# kinx.net
KiCad netlist of a schematic drawn in EAGLE
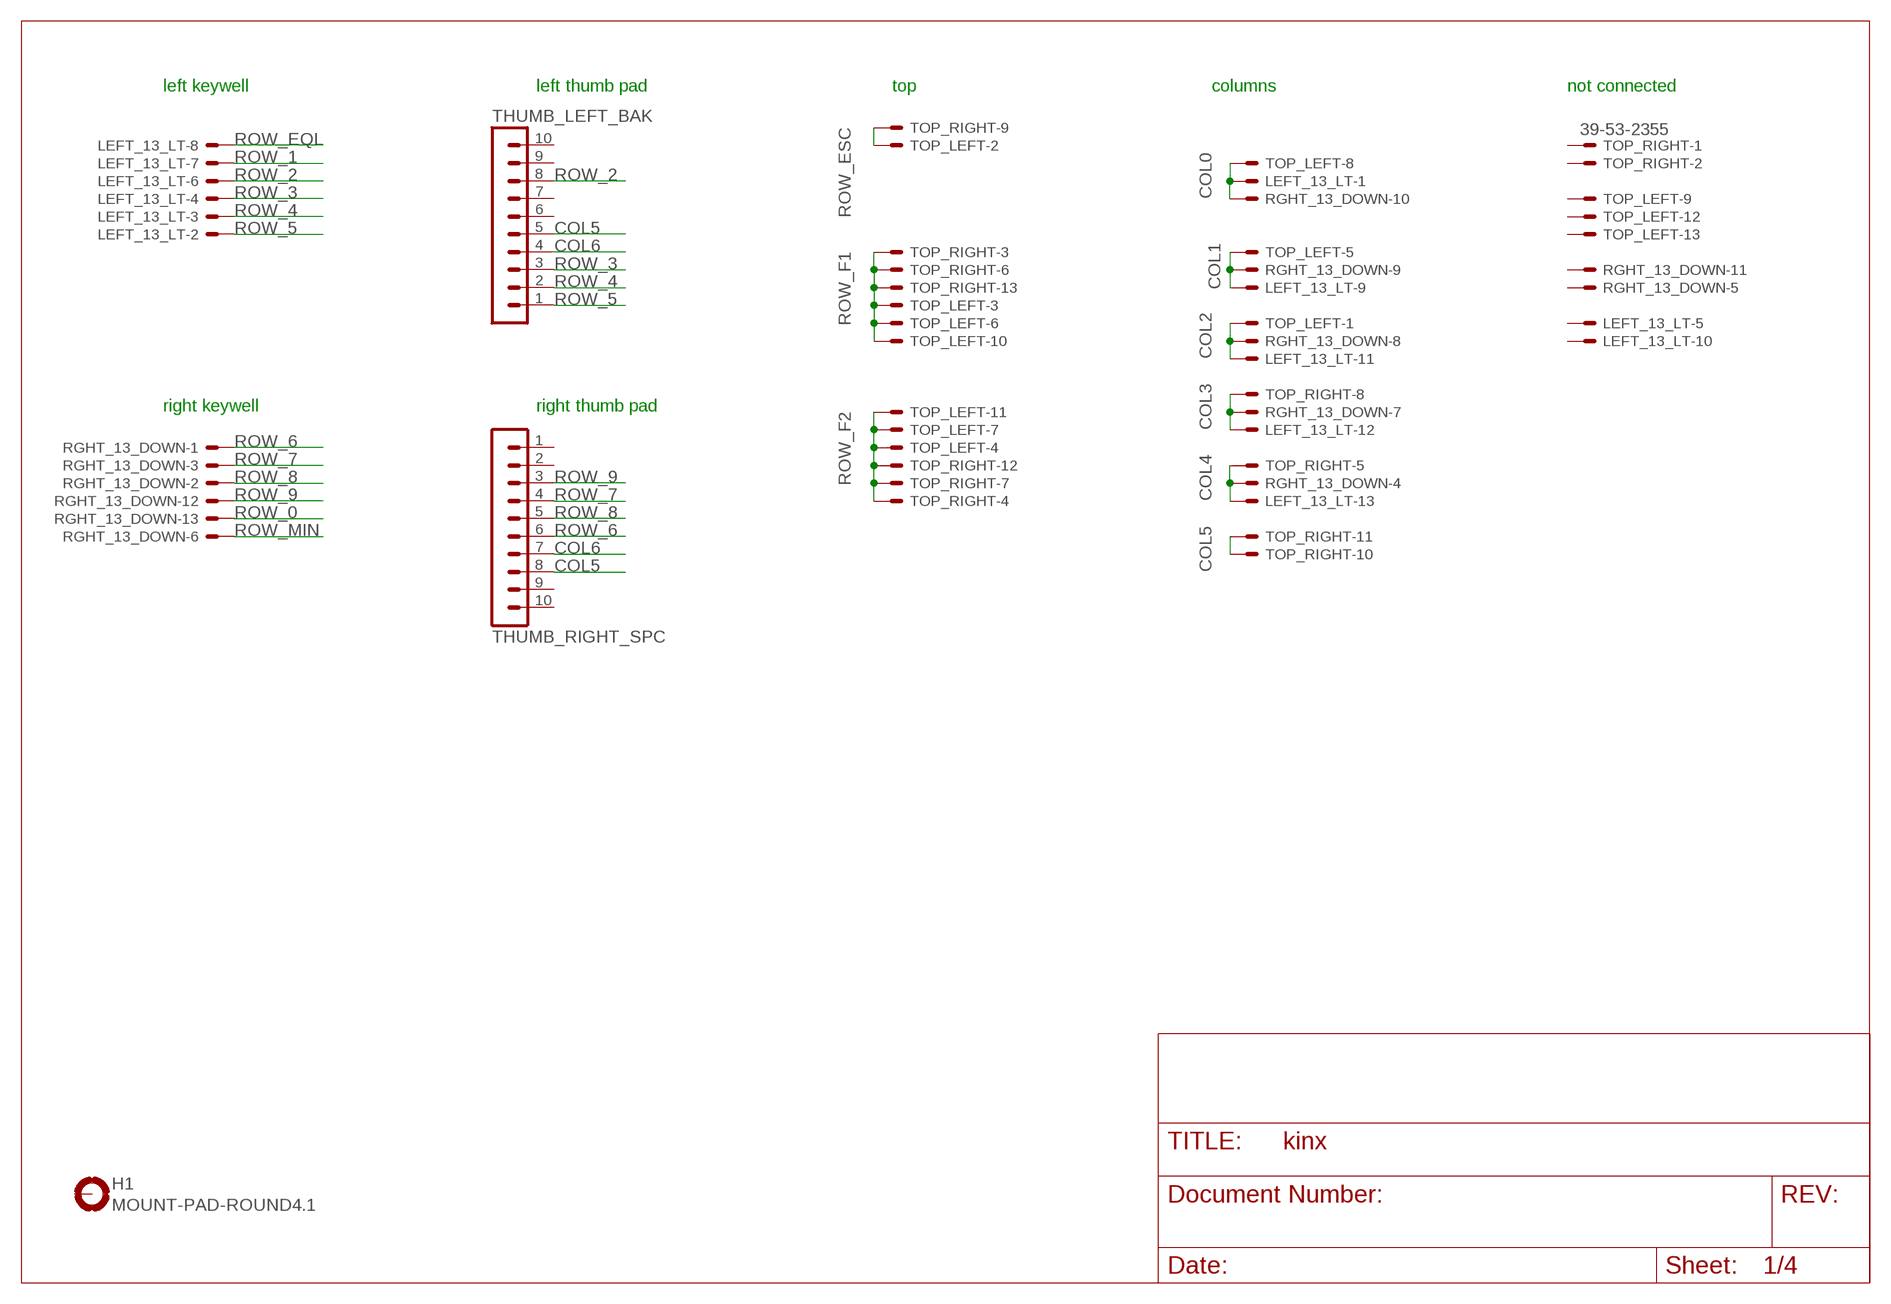
[diagram p0: schematic, sheet 1]
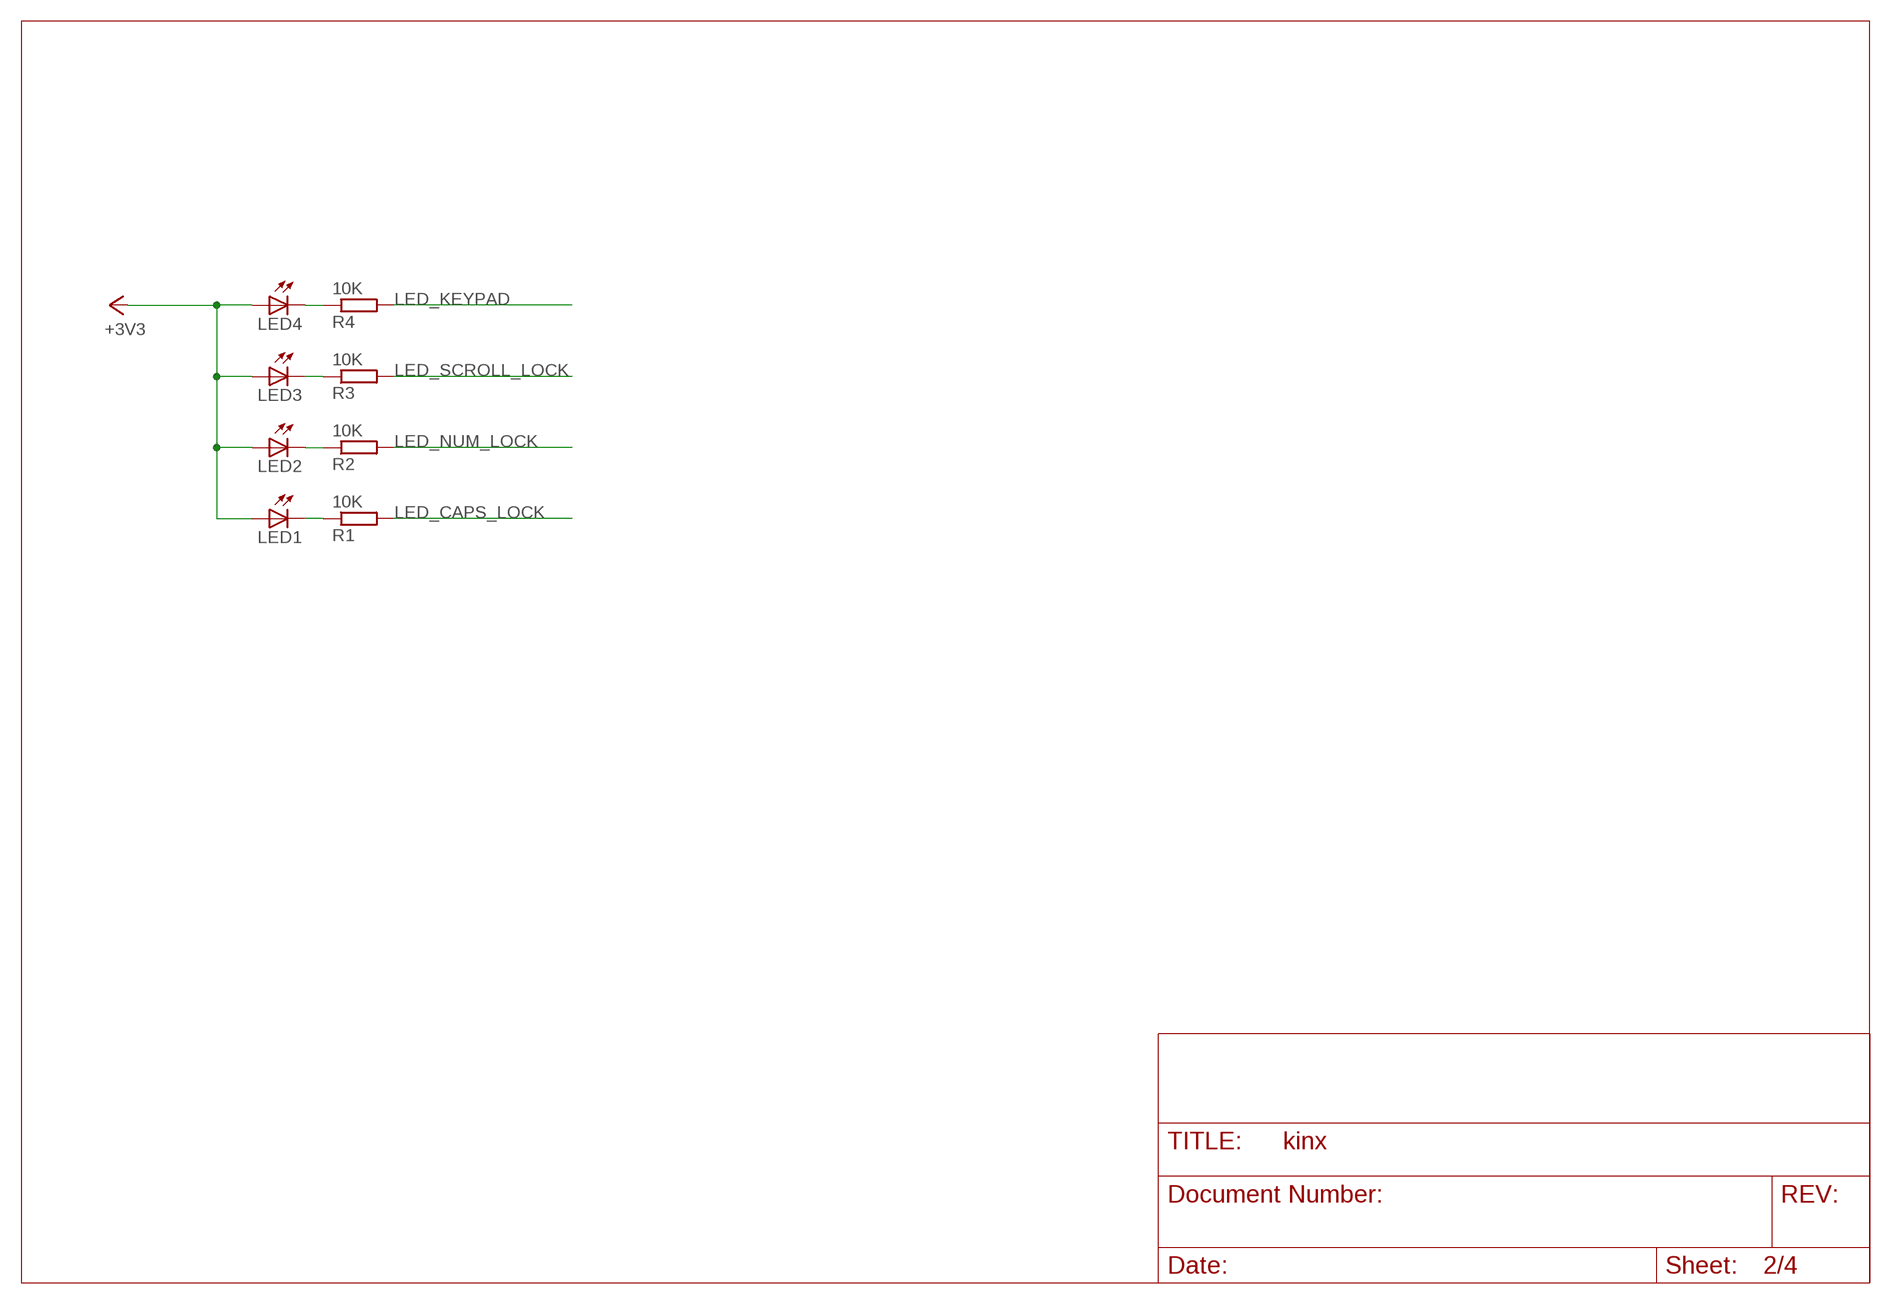
[diagram p1: schematic, sheet 2]
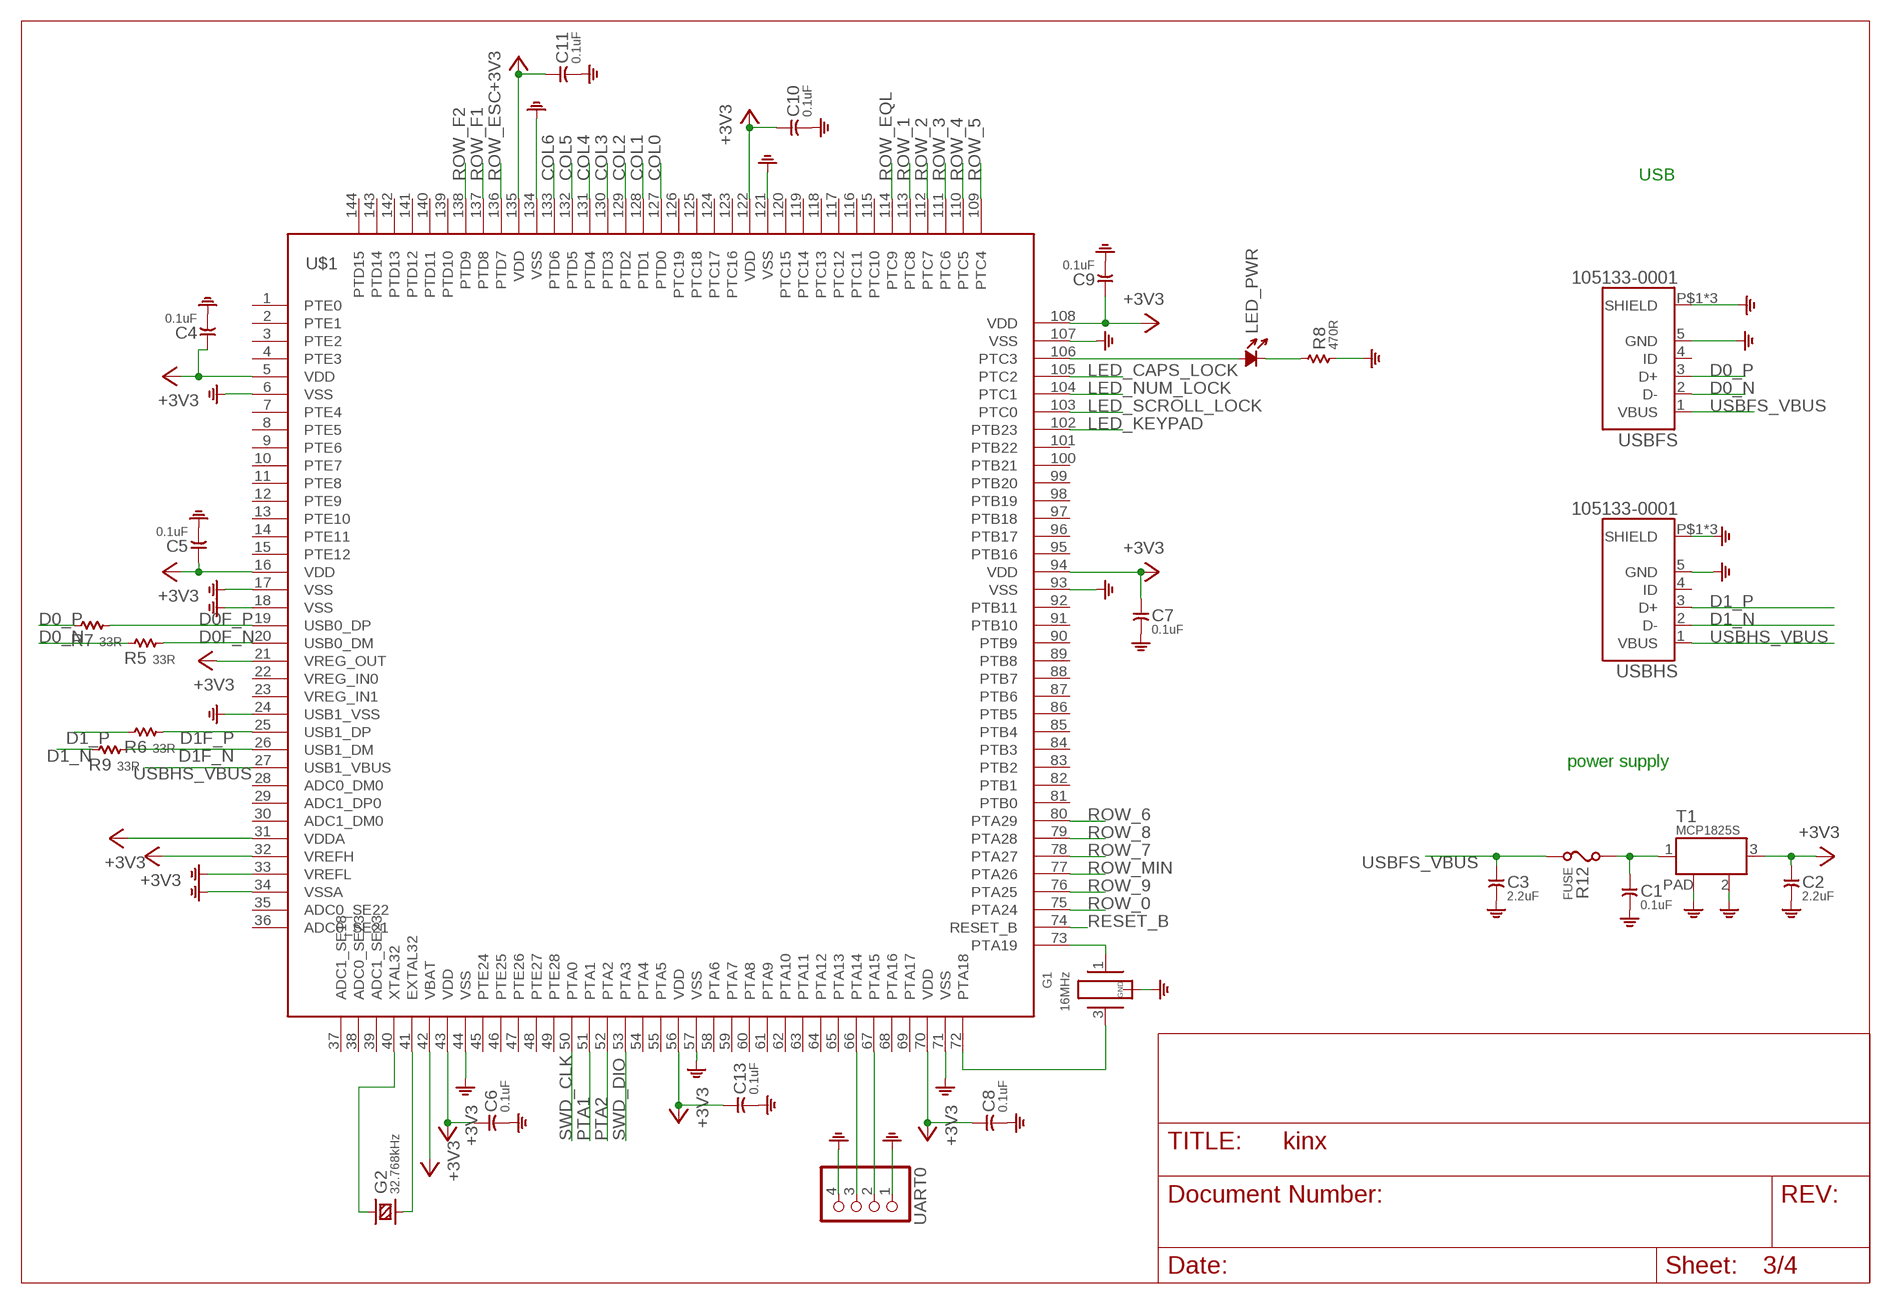
[diagram p2: schematic, sheet 3]
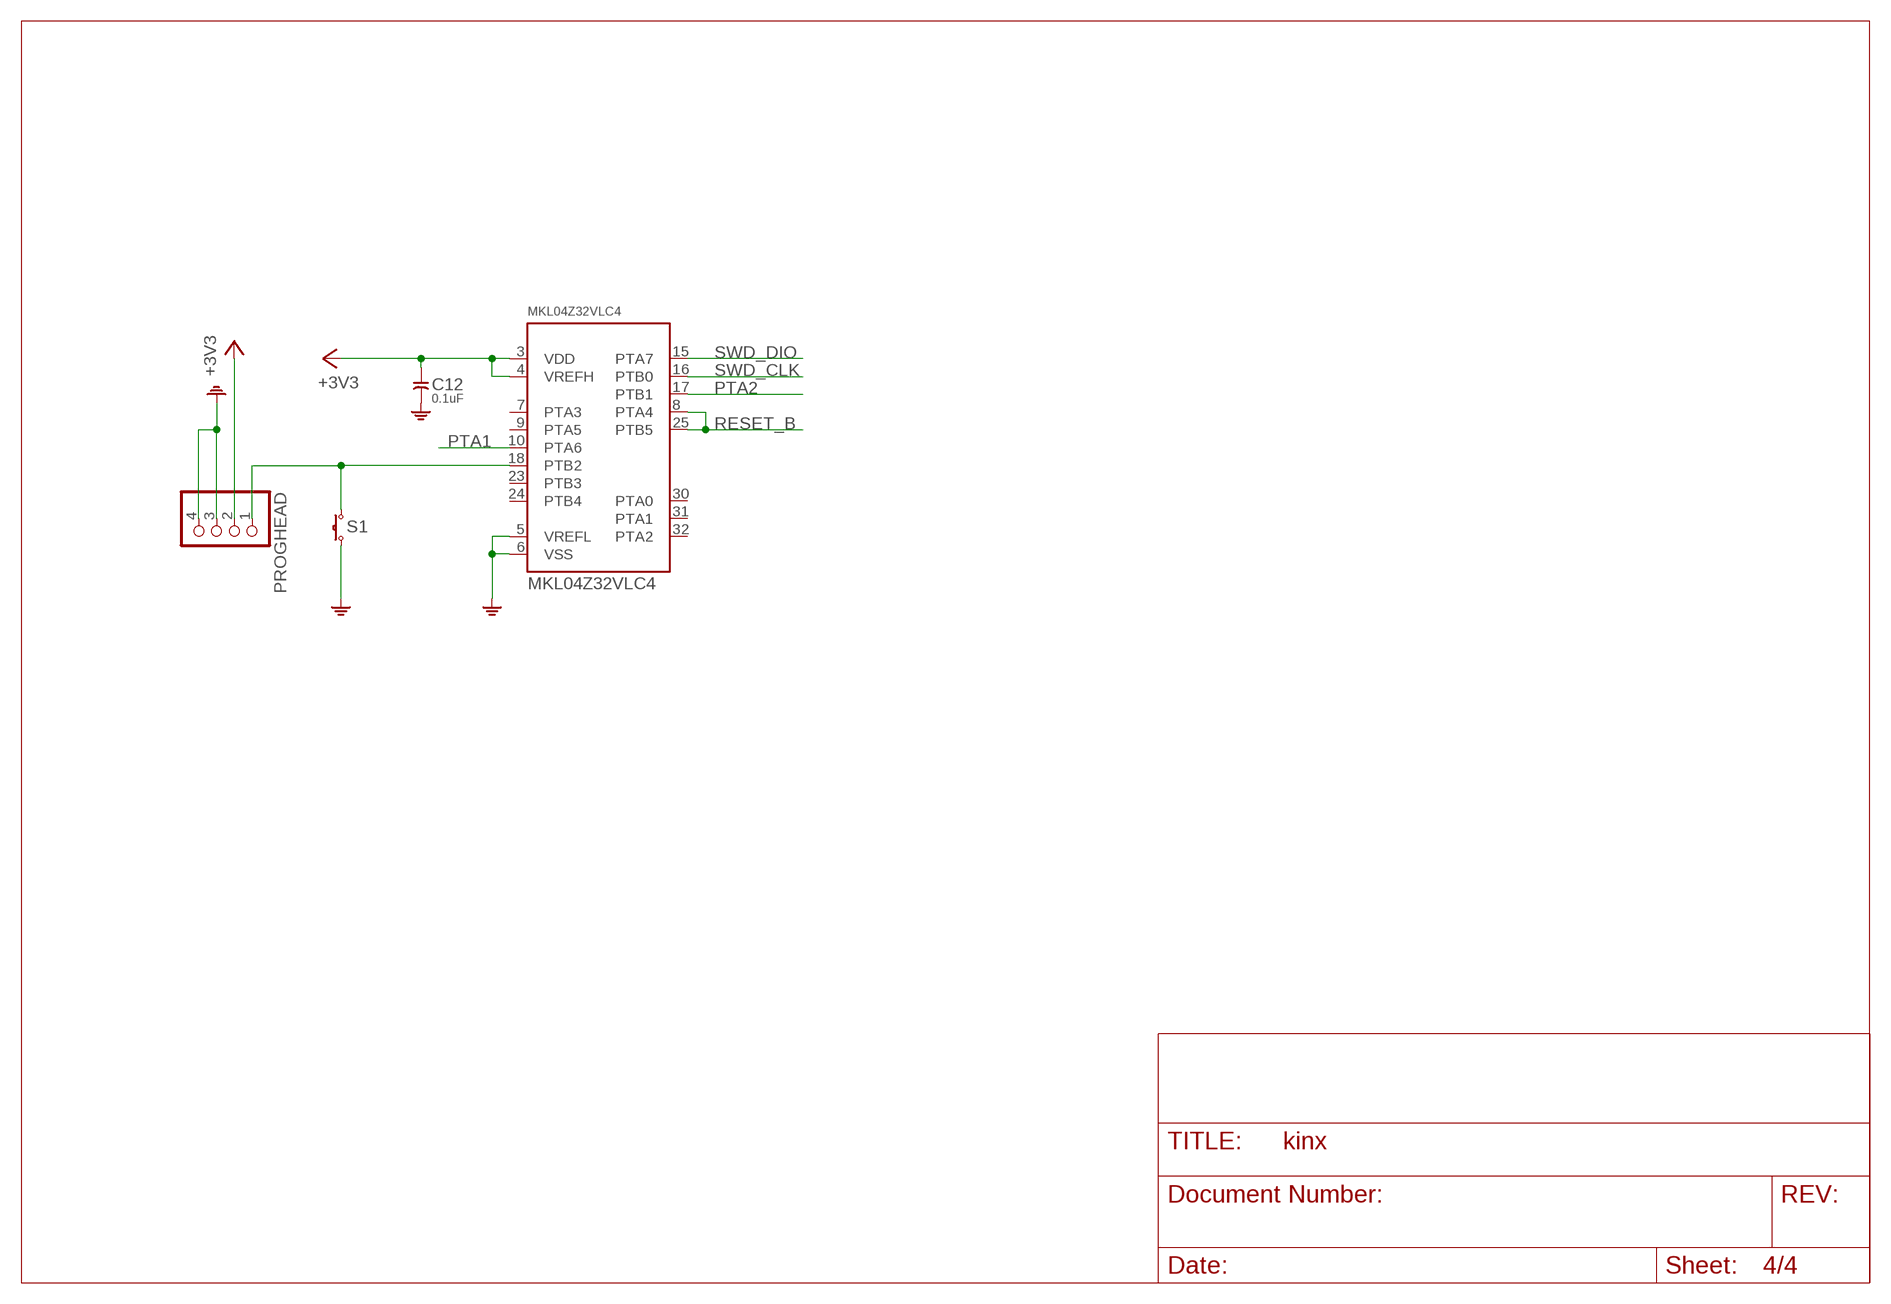
[diagram p3: schematic, sheet 4]

(export (version "E")
  (design (tool "Eeschema 10.0.6"))
  (components
    (comp (ref "LED1")
      (value "LEDSML1206")
      (footprint "eagle-import:SML1206")
      (libsource (lib "eagle-import") (part "LEDSML1206"))
    )
    (comp (ref "LED2")
      (value "LEDSML1206")
      (footprint "eagle-import:SML1206")
      (libsource (lib "eagle-import") (part "LEDSML1206"))
    )
    (comp (ref "LED3")
      (value "LEDSML1206")
      (footprint "eagle-import:SML1206")
      (libsource (lib "eagle-import") (part "LEDSML1206"))
    )
    (comp (ref "LED4")
      (value "LEDSML1206")
      (footprint "eagle-import:SML1206")
      (libsource (lib "eagle-import") (part "LEDSML1206"))
    )
    (comp (ref "R1")
      (value "10K")
      (footprint "eagle-import:R1206")
      (libsource (lib "eagle-import") (part "R-EU_R1206"))
    )
    (comp (ref "R2")
      (value "10K")
      (footprint "eagle-import:R1206")
      (libsource (lib "eagle-import") (part "R-EU_R1206"))
    )
    (comp (ref "R3")
      (value "10K")
      (footprint "eagle-import:R1206")
      (libsource (lib "eagle-import") (part "R-EU_R1206"))
    )
    (comp (ref "R4")
      (value "10K")
      (footprint "eagle-import:R1206")
      (libsource (lib "eagle-import") (part "R-EU_R1206"))
    )
    (comp (ref "C12")
      (value "0.1uF")
      (footprint "eagle-import:C0603")
      (fields (field (name "MF") "Murata Electronics") (field (name "MPN") "GRM188R71C104KA01D"))
      (libsource (lib "eagle-import") (part "CAPACITOR-0.1UF"))
    )
    (comp (ref "MKL04Z32VLC4")
      (value "MKL04Z32VLC4")
      (footprint "eagle-import:LQFP32-08")
      (fields (field (name "MF") "PJRC") (field (name "MPN") "IC_MKL04Z32_TQFP32"))
      (libsource (lib "eagle-import") (part "MKL04Z32VLC4"))
    )
    (comp (ref "PROGHEAD")
      (value "PINHD-1X4/90")
      (footprint "eagle-import:1X04_90")
      (libsource (lib "eagle-import") (part "PINHD-1X4/90"))
    )
    (comp (ref "S1")
      (value "TACT_SWITCH")
      (footprint "eagle-import:ALPS_SKHH")
      (fields (field (name "MF") "ALPS") (field (name "MPN") "SKHHPKA010"))
      (libsource (lib "eagle-import") (part "TACT_SWITCH"))
    )
    (comp (ref "C1")
      (value "0.1uF")
      (footprint "eagle-import:C0603")
      (fields (field (name "MF") "Murata Electronics") (field (name "MPN") "GRM188R71C104KA01D"))
      (libsource (lib "eagle-import") (part "CAPACITOR-0.1UF"))
    )
    (comp (ref "C2")
      (value "2.2uF")
      (footprint "eagle-import:C0805")
      (fields (field (name "MF") "Taiyo Yuden") (field (name "MPN") "TMK212B7225KG-TR"))
      (libsource (lib "eagle-import") (part "CAPACITOR-2.2UF"))
    )
    (comp (ref "C3")
      (value "2.2uF")
      (footprint "eagle-import:C0805")
      (fields (field (name "MF") "Taiyo Yuden") (field (name "MPN") "TMK212B7225KG-TR"))
      (libsource (lib "eagle-import") (part "CAPACITOR-2.2UF"))
    )
    (comp (ref "C4")
      (value "0.1uF")
      (footprint "eagle-import:C0603")
      (fields (field (name "MF") "Murata Electronics") (field (name "MPN") "GRM188R71C104KA01D"))
      (libsource (lib "eagle-import") (part "CAPACITOR-0.1UF"))
    )
    (comp (ref "C5")
      (value "0.1uF")
      (footprint "eagle-import:C0603")
      (fields (field (name "MF") "Murata Electronics") (field (name "MPN") "GRM188R71C104KA01D"))
      (libsource (lib "eagle-import") (part "CAPACITOR-0.1UF"))
    )
    (comp (ref "C6")
      (value "0.1uF")
      (footprint "eagle-import:C0603")
      (fields (field (name "MF") "Murata Electronics") (field (name "MPN") "GRM188R71C104KA01D"))
      (libsource (lib "eagle-import") (part "CAPACITOR-0.1UF"))
    )
    (comp (ref "C7")
      (value "0.1uF")
      (footprint "eagle-import:C0603")
      (fields (field (name "MF") "Murata Electronics") (field (name "MPN") "GRM188R71C104KA01D"))
      (libsource (lib "eagle-import") (part "CAPACITOR-0.1UF"))
    )
    (comp (ref "C8")
      (value "0.1uF")
      (footprint "eagle-import:C0603")
      (fields (field (name "MF") "Murata Electronics") (field (name "MPN") "GRM188R71C104KA01D"))
      (libsource (lib "eagle-import") (part "CAPACITOR-0.1UF"))
    )
    (comp (ref "C9")
      (value "0.1uF")
      (footprint "eagle-import:C0603")
      (fields (field (name "MF") "Murata Electronics") (field (name "MPN") "GRM188R71C104KA01D"))
      (libsource (lib "eagle-import") (part "CAPACITOR-0.1UF"))
    )
    (comp (ref "C10")
      (value "0.1uF")
      (footprint "eagle-import:C0603")
      (fields (field (name "MF") "Murata Electronics") (field (name "MPN") "GRM188R71C104KA01D"))
      (libsource (lib "eagle-import") (part "CAPACITOR-0.1UF"))
    )
    (comp (ref "C11")
      (value "0.1uF")
      (footprint "eagle-import:C0603")
      (fields (field (name "MF") "Murata Electronics") (field (name "MPN") "GRM188R71C104KA01D"))
      (libsource (lib "eagle-import") (part "CAPACITOR-0.1UF"))
    )
    (comp (ref "C13")
      (value "0.1uF")
      (footprint "eagle-import:C0603")
      (fields (field (name "MF") "Murata Electronics") (field (name "MPN") "GRM188R71C104KA01D"))
      (libsource (lib "eagle-import") (part "CAPACITOR-0.1UF"))
    )
    (comp (ref "G1")
      (value "16MHz")
      (footprint "eagle-import:FHXXX")
      (fields
        (field (name "MANUFACTURER") "Diodes Incorporated")
        (field (name "MPN") "FH1600015")
        (field (name "DIGIKEY") "SER4068CT-ND")
      )
      (libsource (lib "eagle-import") (part "FH1600015"))
    )
    (comp (ref "G2")
      (value "32.768kHz")
      (footprint "eagle-import:TC26H")
      (fields (field (name "MF") "Citizen FineDevice") (field (name "MPN") " CFS206-32.768KDZF-UB"))
      (libsource (lib "eagle-import") (part "CRYSTAL-TC26H"))
    )
    (comp (ref "LED_PWR")
      (value "LED")
      (footprint "eagle-import:LED-0805")
      (fields (field (name "MF") "ROHM Semiconductor") (field (name "MPN") "SML-211DTT86"))
      (libsource (lib "eagle-import") (part "t32_ref_LED"))
    )
    (comp (ref "R5")
      (value "33R")
      (footprint "eagle-import:R0603")
      (fields (field (name "MF") "Panasonic") (field (name "MPN") "ERJ-PA3F33R0V"))
      (libsource (lib "eagle-import") (part "RESISTOR-33R"))
    )
    (comp (ref "R6")
      (value "33R")
      (footprint "eagle-import:R0603")
      (fields (field (name "MF") "Panasonic") (field (name "MPN") "ERJ-PA3F33R0V"))
      (libsource (lib "eagle-import") (part "RESISTOR-33R"))
    )
    (comp (ref "R7")
      (value "33R")
      (footprint "eagle-import:R0603")
      (fields (field (name "MF") "Panasonic") (field (name "MPN") "ERJ-PA3F33R0V"))
      (libsource (lib "eagle-import") (part "RESISTOR-33R"))
    )
    (comp (ref "R8")
      (value "470R")
      (footprint "eagle-import:R0603")
      (fields (field (name "MF") "Vishay") (field (name "MPN") "CRCW0603470RFKEA"))
      (libsource (lib "eagle-import") (part "RESISTOR-470R"))
    )
    (comp (ref "R9")
      (value "33R")
      (footprint "eagle-import:R0603")
      (fields (field (name "MF") "Panasonic") (field (name "MPN") "ERJ-PA3F33R0V"))
      (libsource (lib "eagle-import") (part "RESISTOR-33R"))
    )
    (comp (ref "R12")
      (value "FUSE")
      (footprint "eagle-import:F0805")
      (fields (field (name "MF") "Bel Fuse") (field (name "MPN") "0ZCK0050FF2E"))
      (libsource (lib "eagle-import") (part "FUSE"))
    )
    (comp (ref "T1")
      (value "MCP1825S")
      (footprint "eagle-import:SOT-223")
      (fields (field (name "MF") "Microchip Technology") (field (name "MPN") "MCP1825S-3302E/DB"))
      (libsource (lib "eagle-import") (part "LDO"))
    )
    (comp (ref "U$1")
      (value "MK66FX1M0VLQ18")
      (footprint "eagle-import:TQFP144")
      (libsource (lib "eagle-import") (part "MK66FX1M0VLQ18"))
    )
    (comp (ref "UART0")
      (value "PINHD-1X4/90")
      (footprint "eagle-import:1X04_90")
      (libsource (lib "eagle-import") (part "PINHD-1X4/90"))
    )
    (comp (ref "USBFS")
      (value "105133-0001")
      (footprint "eagle-import:MOLEX_105133-0001")
      (fields (field (name "MF") "Molex") (field (name "MP") "105133-0011"))
      (libsource (lib "eagle-import") (part "105133-0001"))
    )
    (comp (ref "USBHS")
      (value "105133-0001")
      (footprint "eagle-import:MOLEX_105133-0001")
      (fields (field (name "MF") "Molex") (field (name "MP") "105133-0011"))
      (libsource (lib "eagle-import") (part "105133-0001"))
    )
    (comp (ref "H1")
      (value "MOUNT-PAD-ROUND4.1")
      (footprint "eagle-import:4,1-PAD")
      (libsource (lib "eagle-import") (part "MOUNT-PAD-ROUND4.1"))
    )
    (comp (ref "LEFT_13_LT")
      (value "39-53-2355")
      (footprint "eagle-import:39-53-2135")
      (fields (field (name "OC_MOUSER") "538-39-53-2135") (field (name "DIGIKEY") "WM14526-ND"))
      (libsource (lib "eagle-import") (part "39-53-2355"))
    )
    (comp (ref "RGHT_13_DOWN")
      (value "39-53-2355")
      (footprint "eagle-import:39-53-2135")
      (fields (field (name "DIGIKEY") "WM14526-ND") (field (name "OC_MOUSER") "538-39-53-2135"))
      (libsource (lib "eagle-import") (part "39-53-2355"))
    )
    (comp (ref "THUMB_LEFT_BAK")
      (value "MA10-1")
      (footprint "eagle-import:MA10-1")
      (libsource (lib "eagle-import") (part "MA10-1"))
    )
    (comp (ref "THUMB_RIGHT_SPC")
      (value "MA10-1")
      (footprint "eagle-import:MA10-1")
      (libsource (lib "eagle-import") (part "MA10-1"))
    )
    (comp (ref "TOP_LEFT")
      (value "39-53-2355")
      (footprint "eagle-import:39-53-2135")
      (fields (field (name "DIGIKEY") "WM14526-ND") (field (name "OC_MOUSER") "538-39-53-2135"))
      (libsource (lib "eagle-import") (part "39-53-2355"))
    )
    (comp (ref "TOP_RIGHT")
      (value "39-53-2355")
      (footprint "eagle-import:39-53-2135")
      (fields (field (name "DIGIKEY") "WM14526-ND") (field (name "OC_MOUSER") "538-39-53-2135"))
      (libsource (lib "eagle-import") (part "39-53-2355"))
    )
  )
  (nets
    (net (code "1") (name "+3V3") (class "Default")
      (node (ref "C10") (pin "1") (pinfunction "1_1") (pintype "passive"))
      (node (ref "C11") (pin "1") (pinfunction "1_1") (pintype "passive"))
      (node (ref "C12") (pin "1") (pinfunction "1_1") (pintype "passive"))
      (node (ref "C13") (pin "1") (pinfunction "1_1") (pintype "passive"))
      (node (ref "C2") (pin "1") (pinfunction "1_1") (pintype "passive"))
      (node (ref "C4") (pin "1") (pinfunction "1_1") (pintype "passive"))
      (node (ref "C5") (pin "1") (pinfunction "1_1") (pintype "passive"))
      (node (ref "C6") (pin "1") (pinfunction "1_1") (pintype "passive"))
      (node (ref "C7") (pin "1") (pinfunction "1_1") (pintype "passive"))
      (node (ref "C8") (pin "1") (pinfunction "1_1") (pintype "passive"))
      (node (ref "C9") (pin "1") (pinfunction "1_1") (pintype "passive"))
      (node (ref "LED1") (pin "A") (pinfunction "A_A") (pintype "passive"))
      (node (ref "LED2") (pin "A") (pinfunction "A_A") (pintype "passive"))
      (node (ref "LED3") (pin "A") (pinfunction "A_A") (pintype "passive"))
      (node (ref "LED4") (pin "A") (pinfunction "A_A") (pintype "passive"))
      (node (ref "MKL04Z32VLC4") (pin "3") (pinfunction "VDD_3") (pintype "bidirectional"))
      (node (ref "MKL04Z32VLC4") (pin "4") (pinfunction "VREFH_4") (pintype "bidirectional"))
      (node (ref "PROGHEAD") (pin "2") (pinfunction "2_2") (pintype "passive"))
      (node (ref "T1") (pin "3") (pinfunction "OUT_3") (pintype "bidirectional"))
      (node (ref "U$1") (pin "108") (pinfunction "VDD_108") (pintype "power_in"))
      (node (ref "U$1") (pin "122") (pinfunction "VDD_122") (pintype "power_in"))
      (node (ref "U$1") (pin "135") (pinfunction "VDD_135") (pintype "power_in"))
      (node (ref "U$1") (pin "16") (pinfunction "VDD_16") (pintype "power_in"))
      (node (ref "U$1") (pin "21") (pinfunction "VREG_OUT_21") (pintype "power_in"))
      (node (ref "U$1") (pin "31") (pinfunction "VDDA_31") (pintype "power_in"))
      (node (ref "U$1") (pin "32") (pinfunction "VREFH_32") (pintype "bidirectional"))
      (node (ref "U$1") (pin "42") (pinfunction "VBAT_42") (pintype "power_in"))
      (node (ref "U$1") (pin "43") (pinfunction "VDD_43") (pintype "power_in"))
      (node (ref "U$1") (pin "5") (pinfunction "VDD_5") (pintype "power_in"))
      (node (ref "U$1") (pin "56") (pinfunction "VDD_56") (pintype "power_in"))
      (node (ref "U$1") (pin "70") (pinfunction "VDD_70") (pintype "power_in"))
      (node (ref "U$1") (pin "94") (pinfunction "VDD_94") (pintype "power_in"))
    )
    (net (code "2") (name "COL0") (class "Default")
      (node (ref "LEFT_13_LT") (pin "P$1") (pinfunction "S_P$1") (pintype "passive"))
      (node (ref "RGHT_13_DOWN") (pin "P$10") (pinfunction "S_P$10") (pintype "passive"))
      (node (ref "TOP_LEFT") (pin "P$8") (pinfunction "S_P$8") (pintype "passive"))
      (node (ref "U$1") (pin "127") (pinfunction "PTD0_127") (pintype "bidirectional"))
    )
    (net (code "3") (name "COL1") (class "Default")
      (node (ref "LEFT_13_LT") (pin "P$9") (pinfunction "S_P$9") (pintype "passive"))
      (node (ref "RGHT_13_DOWN") (pin "P$9") (pinfunction "S_P$9") (pintype "passive"))
      (node (ref "TOP_LEFT") (pin "P$5") (pinfunction "S_P$5") (pintype "passive"))
      (node (ref "U$1") (pin "128") (pinfunction "PTD1_128") (pintype "bidirectional"))
    )
    (net (code "4") (name "COL2") (class "Default")
      (node (ref "LEFT_13_LT") (pin "P$11") (pinfunction "S_P$11") (pintype "passive"))
      (node (ref "RGHT_13_DOWN") (pin "P$8") (pinfunction "S_P$8") (pintype "passive"))
      (node (ref "TOP_LEFT") (pin "P$1") (pinfunction "S_P$1") (pintype "passive"))
      (node (ref "U$1") (pin "129") (pinfunction "PTD2_129") (pintype "bidirectional"))
    )
    (net (code "5") (name "COL3") (class "Default")
      (node (ref "LEFT_13_LT") (pin "P$12") (pinfunction "S_P$12") (pintype "passive"))
      (node (ref "RGHT_13_DOWN") (pin "P$7") (pinfunction "S_P$7") (pintype "passive"))
      (node (ref "TOP_RIGHT") (pin "P$8") (pinfunction "S_P$8") (pintype "passive"))
      (node (ref "U$1") (pin "130") (pinfunction "PTD3_130") (pintype "bidirectional"))
    )
    (net (code "6") (name "COL4") (class "Default")
      (node (ref "LEFT_13_LT") (pin "P$13") (pinfunction "S_P$13") (pintype "passive"))
      (node (ref "RGHT_13_DOWN") (pin "P$4") (pinfunction "S_P$4") (pintype "passive"))
      (node (ref "TOP_RIGHT") (pin "P$5") (pinfunction "S_P$5") (pintype "passive"))
      (node (ref "U$1") (pin "131") (pinfunction "PTD4_131") (pintype "bidirectional"))
    )
    (net (code "7") (name "COL5") (class "Default")
      (node (ref "THUMB_LEFT_BAK") (pin "5") (pinfunction "5_5") (pintype "passive"))
      (node (ref "THUMB_RIGHT_SPC") (pin "8") (pinfunction "8_8") (pintype "passive"))
      (node (ref "TOP_RIGHT") (pin "P$10") (pinfunction "S_P$10") (pintype "passive"))
      (node (ref "TOP_RIGHT") (pin "P$11") (pinfunction "S_P$11") (pintype "passive"))
      (node (ref "U$1") (pin "132") (pinfunction "PTD5_132") (pintype "bidirectional"))
    )
    (net (code "8") (name "COL6") (class "Default")
      (node (ref "THUMB_LEFT_BAK") (pin "4") (pinfunction "4_4") (pintype "passive"))
      (node (ref "THUMB_RIGHT_SPC") (pin "7") (pinfunction "7_7") (pintype "passive"))
      (node (ref "U$1") (pin "133") (pinfunction "PTD6_133") (pintype "bidirectional"))
    )
    (net (code "9") (name "D0F_N") (class "Default")
      (node (ref "R5") (pin "2") (pinfunction "2_2") (pintype "passive"))
      (node (ref "U$1") (pin "20") (pinfunction "USB0_DM_20") (pintype "bidirectional"))
    )
    (net (code "10") (name "D0F_P") (class "Default")
      (node (ref "R7") (pin "2") (pinfunction "2_2") (pintype "passive"))
      (node (ref "U$1") (pin "19") (pinfunction "USB0_DP_19") (pintype "bidirectional"))
    )
    (net (code "11") (name "D0_N") (class "Default")
      (node (ref "R5") (pin "1") (pinfunction "1_1") (pintype "passive"))
      (node (ref "USBFS") (pin "2") (pinfunction "D-_2") (pintype "bidirectional"))
    )
    (net (code "12") (name "D0_P") (class "Default")
      (node (ref "R7") (pin "1") (pinfunction "1_1") (pintype "passive"))
      (node (ref "USBFS") (pin "3") (pinfunction "D+_3") (pintype "bidirectional"))
    )
    (net (code "13") (name "D1F_N") (class "Default")
      (node (ref "R9") (pin "2") (pinfunction "2_2") (pintype "passive"))
      (node (ref "U$1") (pin "26") (pinfunction "USB1_DM_26") (pintype "bidirectional"))
    )
    (net (code "14") (name "D1F_P") (class "Default")
      (node (ref "R6") (pin "2") (pinfunction "2_2") (pintype "passive"))
      (node (ref "U$1") (pin "25") (pinfunction "USB1_DP_25") (pintype "bidirectional"))
    )
    (net (code "15") (name "D1_N") (class "Default")
      (node (ref "R9") (pin "1") (pinfunction "1_1") (pintype "passive"))
      (node (ref "USBHS") (pin "2") (pinfunction "D-_2") (pintype "bidirectional"))
    )
    (net (code "16") (name "D1_P") (class "Default")
      (node (ref "R6") (pin "1") (pinfunction "1_1") (pintype "passive"))
      (node (ref "USBHS") (pin "3") (pinfunction "D+_3") (pintype "bidirectional"))
    )
    (net (code "17") (name "GND") (class "Default")
      (node (ref "C1") (pin "2") (pinfunction "2_2") (pintype "passive"))
      (node (ref "C10") (pin "2") (pinfunction "2_2") (pintype "passive"))
      (node (ref "C11") (pin "2") (pinfunction "2_2") (pintype "passive"))
      (node (ref "C12") (pin "2") (pinfunction "2_2") (pintype "passive"))
      (node (ref "C13") (pin "2") (pinfunction "2_2") (pintype "passive"))
      (node (ref "C2") (pin "2") (pinfunction "2_2") (pintype "passive"))
      (node (ref "C3") (pin "2") (pinfunction "2_2") (pintype "passive"))
      (node (ref "C4") (pin "2") (pinfunction "2_2") (pintype "passive"))
      (node (ref "C5") (pin "2") (pinfunction "2_2") (pintype "passive"))
      (node (ref "C6") (pin "2") (pinfunction "2_2") (pintype "passive"))
      (node (ref "C7") (pin "2") (pinfunction "2_2") (pintype "passive"))
      (node (ref "C8") (pin "2") (pinfunction "2_2") (pintype "passive"))
      (node (ref "C9") (pin "2") (pinfunction "2_2") (pintype "passive"))
      (node (ref "G1") (pin "2") (pinfunction "GND_2") (pintype "bidirectional"))
      (node (ref "G1") (pin "4") (pinfunction "GND_4") (pintype "bidirectional"))
      (node (ref "MKL04Z32VLC4") (pin "5") (pinfunction "VREFL_5") (pintype "bidirectional"))
      (node (ref "MKL04Z32VLC4") (pin "6") (pinfunction "VSS_6") (pintype "bidirectional"))
      (node (ref "PROGHEAD") (pin "3") (pinfunction "3_3") (pintype "passive"))
      (node (ref "PROGHEAD") (pin "4") (pinfunction "4_4") (pintype "passive"))
      (node (ref "R8") (pin "1") (pinfunction "1_1") (pintype "passive"))
      (node (ref "S1") (pin "3") (pinfunction "3_3") (pintype "passive"))
      (node (ref "S1") (pin "4") (pinfunction "3_4") (pintype "passive"))
      (node (ref "T1") (pin "2") (pinfunction "GND_2") (pintype "bidirectional"))
      (node (ref "T1") (pin "PAD") (pinfunction "PAD_PAD") (pintype "bidirectional"))
      (node (ref "U$1") (pin "107") (pinfunction "VSS_107") (pintype "power_in"))
      (node (ref "U$1") (pin "121") (pinfunction "VSS_121") (pintype "power_in"))
      (node (ref "U$1") (pin "134") (pinfunction "VSS_134") (pintype "power_in"))
      (node (ref "U$1") (pin "17") (pinfunction "VSS_17") (pintype "power_in"))
      (node (ref "U$1") (pin "18") (pinfunction "VSS_18") (pintype "power_in"))
      (node (ref "U$1") (pin "24") (pinfunction "USB1_VSS_24") (pintype "power_in"))
      (node (ref "U$1") (pin "33") (pinfunction "VREFL_33") (pintype "bidirectional"))
      (node (ref "U$1") (pin "34") (pinfunction "VSSA_34") (pintype "power_in"))
      (node (ref "U$1") (pin "44") (pinfunction "VSS_44") (pintype "power_in"))
      (node (ref "U$1") (pin "57") (pinfunction "VSS_57") (pintype "power_in"))
      (node (ref "U$1") (pin "6") (pinfunction "VSS_6") (pintype "power_in"))
      (node (ref "U$1") (pin "71") (pinfunction "VSS_71") (pintype "power_in"))
      (node (ref "U$1") (pin "93") (pinfunction "VSS_93") (pintype "power_in"))
      (node (ref "UART0") (pin "1") (pinfunction "1_1") (pintype "passive"))
      (node (ref "UART0") (pin "4") (pinfunction "4_4") (pintype "passive"))
      (node (ref "USBFS") (pin "5") (pinfunction "GND_5") (pintype "power_in"))
      (node (ref "USBFS") (pin "P$1") (pinfunction "SHIELD_P$1") (pintype "passive"))
      (node (ref "USBFS") (pin "P$2") (pinfunction "SHIELD_P$2") (pintype "passive"))
      (node (ref "USBFS") (pin "P$3") (pinfunction "SHIELD_P$3") (pintype "passive"))
      (node (ref "USBHS") (pin "5") (pinfunction "GND_5") (pintype "power_in"))
      (node (ref "USBHS") (pin "P$1") (pinfunction "SHIELD_P$1") (pintype "passive"))
      (node (ref "USBHS") (pin "P$2") (pinfunction "SHIELD_P$2") (pintype "passive"))
      (node (ref "USBHS") (pin "P$3") (pinfunction "SHIELD_P$3") (pintype "passive"))
    )
    (net (code "18") (name "LED_CAPS_LOCK") (class "Default")
      (node (ref "R1") (pin "2") (pinfunction "2_2") (pintype "passive"))
      (node (ref "U$1") (pin "105") (pinfunction "PTC2_105") (pintype "bidirectional"))
    )
    (net (code "19") (name "LED_KEYPAD") (class "Default")
      (node (ref "R4") (pin "2") (pinfunction "2_2") (pintype "passive"))
      (node (ref "U$1") (pin "102") (pinfunction "PTB23_102") (pintype "bidirectional"))
    )
    (net (code "20") (name "LED_NUM_LOCK") (class "Default")
      (node (ref "R2") (pin "2") (pinfunction "2_2") (pintype "passive"))
      (node (ref "U$1") (pin "104") (pinfunction "PTC1_104") (pintype "bidirectional"))
    )
    (net (code "21") (name "LED_SCROLL_LOCK") (class "Default")
      (node (ref "R3") (pin "2") (pinfunction "2_2") (pintype "passive"))
      (node (ref "U$1") (pin "103") (pinfunction "PTC0_103") (pintype "bidirectional"))
    )
    (net (code "22") (name "Net-(G1-2)") (class "Default")
      (node (ref "G1") (pin "3") (pinfunction "2_3") (pintype "bidirectional"))
      (node (ref "U$1") (pin "72") (pinfunction "PTA18_72") (pintype "input"))
    )
    (net (code "23") (name "Net-(G2-1)") (class "Default")
      (node (ref "G2") (pin "2") (pinfunction "1_2") (pintype "passive"))
      (node (ref "U$1") (pin "40") (pinfunction "XTAL32_40") (pintype "output"))
    )
    (net (code "24") (name "Net-(G2-2)") (class "Default")
      (node (ref "G2") (pin "1") (pinfunction "2_1") (pintype "passive"))
      (node (ref "U$1") (pin "41") (pinfunction "EXTAL32_41") (pintype "input"))
    )
    (net (code "25") (name "Net-(LED1-PadC)") (class "Default")
      (node (ref "LED1") (pin "C") (pinfunction "C_C") (pintype "passive"))
      (node (ref "R1") (pin "1") (pinfunction "1_1") (pintype "passive"))
    )
    (net (code "26") (name "Net-(LED2-PadC)") (class "Default")
      (node (ref "LED2") (pin "C") (pinfunction "C_C") (pintype "passive"))
      (node (ref "R2") (pin "1") (pinfunction "1_1") (pintype "passive"))
    )
    (net (code "27") (name "Net-(LED3-PadC)") (class "Default")
      (node (ref "LED3") (pin "C") (pinfunction "C_C") (pintype "passive"))
      (node (ref "R3") (pin "1") (pinfunction "1_1") (pintype "passive"))
    )
    (net (code "28") (name "Net-(LED4-PadC)") (class "Default")
      (node (ref "LED4") (pin "C") (pinfunction "C_C") (pintype "passive"))
      (node (ref "R4") (pin "1") (pinfunction "1_1") (pintype "passive"))
    )
    (net (code "29") (name "Net-(LED_PWR-Pad-)") (class "Default")
      (node (ref "LED_PWR") (pin "-") (pinfunction "-_-") (pintype "passive"))
      (node (ref "R8") (pin "2") (pinfunction "2_2") (pintype "passive"))
    )
    (net (code "30") (name "Net-(MKL04Z32VLC4-PTB2)") (class "Default")
      (node (ref "MKL04Z32VLC4") (pin "18") (pinfunction "PTB2_18") (pintype "bidirectional"))
      (node (ref "PROGHEAD") (pin "1") (pinfunction "1_1") (pintype "passive"))
      (node (ref "S1") (pin "1") (pinfunction "1_1") (pintype "passive"))
      (node (ref "S1") (pin "2") (pinfunction "1_2") (pintype "passive"))
    )
    (net (code "31") (name "Net-(T1-IN)") (class "Default")
      (node (ref "C1") (pin "1") (pinfunction "1_1") (pintype "passive"))
      (node (ref "R12") (pin "2") (pinfunction "2_2") (pintype "bidirectional"))
      (node (ref "T1") (pin "1") (pinfunction "IN_1") (pintype "bidirectional"))
    )
    (net (code "32") (name "Net-(U$1-PTA14)") (class "Default")
      (node (ref "U$1") (pin "66") (pinfunction "PTA14_66") (pintype "bidirectional"))
      (node (ref "UART0") (pin "3") (pinfunction "3_3") (pintype "passive"))
    )
    (net (code "33") (name "Net-(U$1-PTA15)") (class "Default")
      (node (ref "U$1") (pin "67") (pinfunction "PTA15_67") (pintype "bidirectional"))
      (node (ref "UART0") (pin "2") (pinfunction "2_2") (pintype "passive"))
    )
    (net (code "34") (name "Net-(U$1-PTA19)") (class "Default")
      (node (ref "G1") (pin "1") (pinfunction "1_1") (pintype "bidirectional"))
      (node (ref "U$1") (pin "73") (pinfunction "PTA19_73") (pintype "output"))
    )
    (net (code "35") (name "Net-(U$1-PTC3)") (class "Default")
      (node (ref "LED_PWR") (pin "+") (pinfunction "+_+") (pintype "passive"))
      (node (ref "U$1") (pin "106") (pinfunction "PTC3_106") (pintype "bidirectional"))
    )
    (net (code "36") (name "PTA1") (class "Default")
      (node (ref "MKL04Z32VLC4") (pin "10") (pinfunction "PTA6_10") (pintype "bidirectional"))
      (node (ref "U$1") (pin "51") (pinfunction "PTA1_51") (pintype "input"))
    )
    (net (code "37") (name "PTA2") (class "Default")
      (node (ref "MKL04Z32VLC4") (pin "17") (pinfunction "PTB1_17") (pintype "bidirectional"))
      (node (ref "U$1") (pin "52") (pinfunction "PTA2_52") (pintype "output"))
    )
    (net (code "38") (name "RESET_B") (class "Default")
      (node (ref "MKL04Z32VLC4") (pin "25") (pinfunction "PTB5_25") (pintype "bidirectional"))
      (node (ref "MKL04Z32VLC4") (pin "8") (pinfunction "PTA4_8") (pintype "bidirectional"))
      (node (ref "U$1") (pin "74") (pinfunction "RESET_B_74") (pintype "bidirectional"))
    )
    (net (code "39") (name "ROW_0") (class "Default")
      (node (ref "RGHT_13_DOWN") (pin "P$13") (pinfunction "S_P$13") (pintype "passive"))
      (node (ref "U$1") (pin "75") (pinfunction "PTA24_75") (pintype "bidirectional"))
    )
    (net (code "40") (name "ROW_1") (class "Default")
      (node (ref "LEFT_13_LT") (pin "P$7") (pinfunction "S_P$7") (pintype "passive"))
      (node (ref "U$1") (pin "113") (pinfunction "PTC8_113") (pintype "bidirectional"))
    )
    (net (code "41") (name "ROW_2") (class "Default")
      (node (ref "LEFT_13_LT") (pin "P$6") (pinfunction "S_P$6") (pintype "passive"))
      (node (ref "THUMB_LEFT_BAK") (pin "8") (pinfunction "8_8") (pintype "passive"))
      (node (ref "U$1") (pin "112") (pinfunction "PTC7_112") (pintype "bidirectional"))
    )
    (net (code "42") (name "ROW_3") (class "Default")
      (node (ref "LEFT_13_LT") (pin "P$4") (pinfunction "S_P$4") (pintype "passive"))
      (node (ref "THUMB_LEFT_BAK") (pin "3") (pinfunction "3_3") (pintype "passive"))
      (node (ref "U$1") (pin "111") (pinfunction "PTC6_111") (pintype "bidirectional"))
    )
    (net (code "43") (name "ROW_4") (class "Default")
      (node (ref "LEFT_13_LT") (pin "P$3") (pinfunction "S_P$3") (pintype "passive"))
      (node (ref "THUMB_LEFT_BAK") (pin "2") (pinfunction "2_2") (pintype "passive"))
      (node (ref "U$1") (pin "110") (pinfunction "PTC5_110") (pintype "bidirectional"))
    )
    (net (code "44") (name "ROW_5") (class "Default")
      (node (ref "LEFT_13_LT") (pin "P$2") (pinfunction "S_P$2") (pintype "passive"))
      (node (ref "THUMB_LEFT_BAK") (pin "1") (pinfunction "1_1") (pintype "passive"))
      (node (ref "U$1") (pin "109") (pinfunction "PTC4_109") (pintype "bidirectional"))
    )
    (net (code "45") (name "ROW_6") (class "Default")
      (node (ref "RGHT_13_DOWN") (pin "P$1") (pinfunction "S_P$1") (pintype "passive"))
      (node (ref "THUMB_RIGHT_SPC") (pin "6") (pinfunction "6_6") (pintype "passive"))
      (node (ref "U$1") (pin "80") (pinfunction "PTA29_80") (pintype "bidirectional"))
    )
    (net (code "46") (name "ROW_7") (class "Default")
      (node (ref "RGHT_13_DOWN") (pin "P$3") (pinfunction "S_P$3") (pintype "passive"))
      (node (ref "THUMB_RIGHT_SPC") (pin "4") (pinfunction "4_4") (pintype "passive"))
      (node (ref "U$1") (pin "78") (pinfunction "PTA27_78") (pintype "bidirectional"))
    )
    (net (code "47") (name "ROW_8") (class "Default")
      (node (ref "RGHT_13_DOWN") (pin "P$2") (pinfunction "S_P$2") (pintype "passive"))
      (node (ref "THUMB_RIGHT_SPC") (pin "5") (pinfunction "5_5") (pintype "passive"))
      (node (ref "U$1") (pin "79") (pinfunction "PTA28_79") (pintype "bidirectional"))
    )
    (net (code "48") (name "ROW_9") (class "Default")
      (node (ref "RGHT_13_DOWN") (pin "P$12") (pinfunction "S_P$12") (pintype "passive"))
      (node (ref "THUMB_RIGHT_SPC") (pin "3") (pinfunction "3_3") (pintype "passive"))
      (node (ref "U$1") (pin "76") (pinfunction "PTA25_76") (pintype "bidirectional"))
    )
    (net (code "49") (name "ROW_EQL") (class "Default")
      (node (ref "LEFT_13_LT") (pin "P$8") (pinfunction "S_P$8") (pintype "passive"))
      (node (ref "U$1") (pin "114") (pinfunction "PTC9_114") (pintype "bidirectional"))
    )
    (net (code "50") (name "ROW_ESC") (class "Default")
      (node (ref "TOP_LEFT") (pin "P$2") (pinfunction "S_P$2") (pintype "passive"))
      (node (ref "TOP_RIGHT") (pin "P$9") (pinfunction "S_P$9") (pintype "passive"))
      (node (ref "U$1") (pin "136") (pinfunction "PTD7_136") (pintype "bidirectional"))
    )
    (net (code "51") (name "ROW_F1") (class "Default")
      (node (ref "TOP_LEFT") (pin "P$10") (pinfunction "S_P$10") (pintype "passive"))
      (node (ref "TOP_LEFT") (pin "P$3") (pinfunction "S_P$3") (pintype "passive"))
      (node (ref "TOP_LEFT") (pin "P$6") (pinfunction "S_P$6") (pintype "passive"))
      (node (ref "TOP_RIGHT") (pin "P$13") (pinfunction "S_P$13") (pintype "passive"))
      (node (ref "TOP_RIGHT") (pin "P$3") (pinfunction "S_P$3") (pintype "passive"))
      (node (ref "TOP_RIGHT") (pin "P$6") (pinfunction "S_P$6") (pintype "passive"))
      (node (ref "U$1") (pin "137") (pinfunction "PTD8_137") (pintype "bidirectional"))
    )
    (net (code "52") (name "ROW_F2") (class "Default")
      (node (ref "TOP_LEFT") (pin "P$11") (pinfunction "S_P$11") (pintype "passive"))
      (node (ref "TOP_LEFT") (pin "P$4") (pinfunction "S_P$4") (pintype "passive"))
      (node (ref "TOP_LEFT") (pin "P$7") (pinfunction "S_P$7") (pintype "passive"))
      (node (ref "TOP_RIGHT") (pin "P$12") (pinfunction "S_P$12") (pintype "passive"))
      (node (ref "TOP_RIGHT") (pin "P$4") (pinfunction "S_P$4") (pintype "passive"))
      (node (ref "TOP_RIGHT") (pin "P$7") (pinfunction "S_P$7") (pintype "passive"))
      (node (ref "U$1") (pin "138") (pinfunction "PTD9_138") (pintype "bidirectional"))
    )
    (net (code "53") (name "ROW_MIN") (class "Default")
      (node (ref "RGHT_13_DOWN") (pin "P$6") (pinfunction "S_P$6") (pintype "passive"))
      (node (ref "U$1") (pin "77") (pinfunction "PTA26_77") (pintype "bidirectional"))
    )
    (net (code "54") (name "SWD_CLK") (class "Default")
      (node (ref "MKL04Z32VLC4") (pin "16") (pinfunction "PTB0_16") (pintype "bidirectional"))
      (node (ref "U$1") (pin "50") (pinfunction "PTA0_50") (pintype "input"))
    )
    (net (code "55") (name "SWD_DIO") (class "Default")
      (node (ref "MKL04Z32VLC4") (pin "15") (pinfunction "PTA7_15") (pintype "bidirectional"))
      (node (ref "U$1") (pin "53") (pinfunction "PTA3_53") (pintype "bidirectional"))
    )
    (net (code "56") (name "USBFS_VBUS") (class "Default")
      (node (ref "C3") (pin "1") (pinfunction "1_1") (pintype "passive"))
      (node (ref "R12") (pin "1") (pinfunction "1_1") (pintype "bidirectional"))
      (node (ref "USBFS") (pin "1") (pinfunction "VBUS_1") (pintype "power_in"))
    )
    (net (code "57") (name "USBHS_VBUS") (class "Default")
      (node (ref "U$1") (pin "27") (pinfunction "USB1_VBUS_27") (pintype "power_in"))
      (node (ref "USBHS") (pin "1") (pinfunction "VBUS_1") (pintype "power_in"))
    )
    (net (code "58") (name "VREG_IN0") (class "Default")
      (node (ref "U$1") (pin "22") (pinfunction "VREG_IN0_22") (pintype "power_in"))
    )
    (net (code "59") (name "VREG_IN1") (class "Default")
      (node (ref "U$1") (pin "23") (pinfunction "VREG_IN1_23") (pintype "power_in"))
    )
    (net (code "60") (name "unconnected-(H1-MOUNT-PadB4,1)") (class "Default")
      (node (ref "H1") (pin "B4,1") (pinfunction "MOUNT_B4,1") (pintype "passive"))
    )
    (net (code "61") (name "unconnected-(LEFT_13_LTB-S-PadP$10)") (class "Default")
      (node (ref "LEFT_13_LT") (pin "P$10") (pinfunction "S_P$10") (pintype "passive"))
    )
    (net (code "62") (name "unconnected-(LEFT_13_LTI-S-PadP$5)") (class "Default")
      (node (ref "LEFT_13_LT") (pin "P$5") (pinfunction "S_P$5") (pintype "passive"))
    )
    (net (code "63") (name "unconnected-(MKL04Z32VLC4-PTA0-Pad30)") (class "Default")
      (node (ref "MKL04Z32VLC4") (pin "30") (pinfunction "PTA0_30") (pintype "bidirectional"))
    )
    (net (code "64") (name "unconnected-(MKL04Z32VLC4-PTA1-Pad31)") (class "Default")
      (node (ref "MKL04Z32VLC4") (pin "31") (pinfunction "PTA1_31") (pintype "bidirectional"))
    )
    (net (code "65") (name "unconnected-(MKL04Z32VLC4-PTA2-Pad32)") (class "Default")
      (node (ref "MKL04Z32VLC4") (pin "32") (pinfunction "PTA2_32") (pintype "bidirectional"))
    )
    (net (code "66") (name "unconnected-(MKL04Z32VLC4-PTA3-Pad7)") (class "Default")
      (node (ref "MKL04Z32VLC4") (pin "7") (pinfunction "PTA3_7") (pintype "bidirectional"))
    )
    (net (code "67") (name "unconnected-(MKL04Z32VLC4-PTA5-Pad9)") (class "Default")
      (node (ref "MKL04Z32VLC4") (pin "9") (pinfunction "PTA5_9") (pintype "bidirectional"))
    )
    (net (code "68") (name "unconnected-(MKL04Z32VLC4-PTB3-Pad23)") (class "Default")
      (node (ref "MKL04Z32VLC4") (pin "23") (pinfunction "PTB3_23") (pintype "bidirectional"))
    )
    (net (code "69") (name "unconnected-(MKL04Z32VLC4-PTB4-Pad24)") (class "Default")
      (node (ref "MKL04Z32VLC4") (pin "24") (pinfunction "PTB4_24") (pintype "bidirectional"))
    )
    (net (code "70") (name "unconnected-(RGHT_13_DOWNC-S-PadP$11)") (class "Default")
      (node (ref "RGHT_13_DOWN") (pin "P$11") (pinfunction "S_P$11") (pintype "passive"))
    )
    (net (code "71") (name "unconnected-(RGHT_13_DOWNI-S-PadP$5)") (class "Default")
      (node (ref "RGHT_13_DOWN") (pin "P$5") (pinfunction "S_P$5") (pintype "passive"))
    )
    (net (code "72") (name "unconnected-(THUMB_LEFT_BAK-Pad6)") (class "Default")
      (node (ref "THUMB_LEFT_BAK") (pin "6") (pinfunction "6_6") (pintype "passive"))
    )
    (net (code "73") (name "unconnected-(THUMB_LEFT_BAK-Pad7)") (class "Default")
      (node (ref "THUMB_LEFT_BAK") (pin "7") (pinfunction "7_7") (pintype "passive"))
    )
    (net (code "74") (name "unconnected-(THUMB_LEFT_BAK-Pad9)") (class "Default")
      (node (ref "THUMB_LEFT_BAK") (pin "9") (pinfunction "9_9") (pintype "passive"))
    )
    (net (code "75") (name "unconnected-(THUMB_LEFT_BAK-Pad10)") (class "Default")
      (node (ref "THUMB_LEFT_BAK") (pin "10") (pinfunction "10_10") (pintype "passive"))
    )
    (net (code "76") (name "unconnected-(THUMB_RIGHT_SPC-Pad1)") (class "Default")
      (node (ref "THUMB_RIGHT_SPC") (pin "1") (pinfunction "1_1") (pintype "passive"))
    )
    (net (code "77") (name "unconnected-(THUMB_RIGHT_SPC-Pad2)") (class "Default")
      (node (ref "THUMB_RIGHT_SPC") (pin "2") (pinfunction "2_2") (pintype "passive"))
    )
    (net (code "78") (name "unconnected-(THUMB_RIGHT_SPC-Pad9)") (class "Default")
      (node (ref "THUMB_RIGHT_SPC") (pin "9") (pinfunction "9_9") (pintype "passive"))
    )
    (net (code "79") (name "unconnected-(THUMB_RIGHT_SPC-Pad10)") (class "Default")
      (node (ref "THUMB_RIGHT_SPC") (pin "10") (pinfunction "10_10") (pintype "passive"))
    )
    (net (code "80") (name "unconnected-(TOP_LEFTD-S-PadP$12)") (class "Default")
      (node (ref "TOP_LEFT") (pin "P$12") (pinfunction "S_P$12") (pintype "passive"))
    )
    (net (code "81") (name "unconnected-(TOP_LEFTE-S-PadP$13)") (class "Default")
      (node (ref "TOP_LEFT") (pin "P$13") (pinfunction "S_P$13") (pintype "passive"))
    )
    (net (code "82") (name "unconnected-(TOP_LEFTM-S-PadP$9)") (class "Default")
      (node (ref "TOP_LEFT") (pin "P$9") (pinfunction "S_P$9") (pintype "passive"))
    )
    (net (code "83") (name "unconnected-(TOP_RIGHTA-S-PadP$1)") (class "Default")
      (node (ref "TOP_RIGHT") (pin "P$1") (pinfunction "S_P$1") (pintype "passive"))
    )
    (net (code "84") (name "unconnected-(TOP_RIGHTF-S-PadP$2)") (class "Default")
      (node (ref "TOP_RIGHT") (pin "P$2") (pinfunction "S_P$2") (pintype "passive"))
    )
    (net (code "85") (name "unconnected-(U$1-ADC0_DM0-Pad28)") (class "Default")
      (node (ref "U$1") (pin "28") (pinfunction "ADC0_DM0_28") (pintype "bidirectional"))
    )
    (net (code "86") (name "unconnected-(U$1-ADC0_SE21-Pad36)") (class "Default")
      (node (ref "U$1") (pin "36") (pinfunction "ADC0_SE21_36") (pintype "bidirectional"))
    )
    (net (code "87") (name "unconnected-(U$1-ADC0_SE22-Pad35)") (class "Default")
      (node (ref "U$1") (pin "35") (pinfunction "ADC0_SE22_35") (pintype "bidirectional"))
    )
    (net (code "88") (name "unconnected-(U$1-ADC0_SE23-Pad38)") (class "Default")
      (node (ref "U$1") (pin "38") (pinfunction "ADC0_SE23_38") (pintype "bidirectional"))
    )
    (net (code "89") (name "unconnected-(U$1-ADC1_DM0-Pad30)") (class "Default")
      (node (ref "U$1") (pin "30") (pinfunction "ADC1_DM0_30") (pintype "bidirectional"))
    )
    (net (code "90") (name "unconnected-(U$1-ADC1_DP0-Pad29)") (class "Default")
      (node (ref "U$1") (pin "29") (pinfunction "ADC1_DP0_29") (pintype "bidirectional"))
    )
    (net (code "91") (name "unconnected-(U$1-ADC1_SE18-Pad37)") (class "Default")
      (node (ref "U$1") (pin "37") (pinfunction "ADC1_SE18_37") (pintype "bidirectional"))
    )
    (net (code "92") (name "unconnected-(U$1-ADC1_SE23-Pad39)") (class "Default")
      (node (ref "U$1") (pin "39") (pinfunction "ADC1_SE23_39") (pintype "bidirectional"))
    )
    (net (code "93") (name "unconnected-(U$1-PTA4-Pad54)") (class "Default")
      (node (ref "U$1") (pin "54") (pinfunction "PTA4_54") (pintype "bidirectional"))
    )
    (net (code "94") (name "unconnected-(U$1-PTA5-Pad55)") (class "Default")
      (node (ref "U$1") (pin "55") (pinfunction "PTA5_55") (pintype "input"))
    )
    (net (code "95") (name "unconnected-(U$1-PTA6-Pad58)") (class "Default")
      (node (ref "U$1") (pin "58") (pinfunction "PTA6_58") (pintype "bidirectional"))
    )
    (net (code "96") (name "unconnected-(U$1-PTA7-Pad59)") (class "Default")
      (node (ref "U$1") (pin "59") (pinfunction "PTA7_59") (pintype "bidirectional"))
    )
    (net (code "97") (name "unconnected-(U$1-PTA8-Pad60)") (class "Default")
      (node (ref "U$1") (pin "60") (pinfunction "PTA8_60") (pintype "bidirectional"))
    )
    (net (code "98") (name "unconnected-(U$1-PTA9-Pad61)") (class "Default")
      (node (ref "U$1") (pin "61") (pinfunction "PTA9_61") (pintype "bidirectional"))
    )
    (net (code "99") (name "unconnected-(U$1-PTA10-Pad62)") (class "Default")
      (node (ref "U$1") (pin "62") (pinfunction "PTA10_62") (pintype "bidirectional"))
    )
    (net (code "100") (name "unconnected-(U$1-PTA11-Pad63)") (class "Default")
      (node (ref "U$1") (pin "63") (pinfunction "PTA11_63") (pintype "bidirectional"))
    )
    (net (code "101") (name "unconnected-(U$1-PTA12-Pad64)") (class "Default")
      (node (ref "U$1") (pin "64") (pinfunction "PTA12_64") (pintype "bidirectional"))
    )
    (net (code "102") (name "unconnected-(U$1-PTA13-Pad65)") (class "Default")
      (node (ref "U$1") (pin "65") (pinfunction "PTA13_65") (pintype "bidirectional"))
    )
    (net (code "103") (name "unconnected-(U$1-PTA16-Pad68)") (class "Default")
      (node (ref "U$1") (pin "68") (pinfunction "PTA16_68") (pintype "bidirectional"))
    )
    (net (code "104") (name "unconnected-(U$1-PTA17-Pad69)") (class "Default")
      (node (ref "U$1") (pin "69") (pinfunction "PTA17_69") (pintype "bidirectional"))
    )
    (net (code "105") (name "unconnected-(U$1-PTB0-Pad81)") (class "Default")
      (node (ref "U$1") (pin "81") (pinfunction "PTB0_81") (pintype "bidirectional"))
    )
    (net (code "106") (name "unconnected-(U$1-PTB1-Pad82)") (class "Default")
      (node (ref "U$1") (pin "82") (pinfunction "PTB1_82") (pintype "bidirectional"))
    )
    (net (code "107") (name "unconnected-(U$1-PTB2-Pad83)") (class "Default")
      (node (ref "U$1") (pin "83") (pinfunction "PTB2_83") (pintype "bidirectional"))
    )
    (net (code "108") (name "unconnected-(U$1-PTB3-Pad84)") (class "Default")
      (node (ref "U$1") (pin "84") (pinfunction "PTB3_84") (pintype "bidirectional"))
    )
    (net (code "109") (name "unconnected-(U$1-PTB4-Pad85)") (class "Default")
      (node (ref "U$1") (pin "85") (pinfunction "PTB4_85") (pintype "bidirectional"))
    )
    (net (code "110") (name "unconnected-(U$1-PTB5-Pad86)") (class "Default")
      (node (ref "U$1") (pin "86") (pinfunction "PTB5_86") (pintype "bidirectional"))
    )
    (net (code "111") (name "unconnected-(U$1-PTB6-Pad87)") (class "Default")
      (node (ref "U$1") (pin "87") (pinfunction "PTB6_87") (pintype "bidirectional"))
    )
    (net (code "112") (name "unconnected-(U$1-PTB7-Pad88)") (class "Default")
      (node (ref "U$1") (pin "88") (pinfunction "PTB7_88") (pintype "bidirectional"))
    )
    (net (code "113") (name "unconnected-(U$1-PTB8-Pad89)") (class "Default")
      (node (ref "U$1") (pin "89") (pinfunction "PTB8_89") (pintype "bidirectional"))
    )
    (net (code "114") (name "unconnected-(U$1-PTB9-Pad90)") (class "Default")
      (node (ref "U$1") (pin "90") (pinfunction "PTB9_90") (pintype "bidirectional"))
    )
    (net (code "115") (name "unconnected-(U$1-PTB10-Pad91)") (class "Default")
      (node (ref "U$1") (pin "91") (pinfunction "PTB10_91") (pintype "bidirectional"))
    )
    (net (code "116") (name "unconnected-(U$1-PTB11-Pad92)") (class "Default")
      (node (ref "U$1") (pin "92") (pinfunction "PTB11_92") (pintype "bidirectional"))
    )
    (net (code "117") (name "unconnected-(U$1-PTB16-Pad95)") (class "Default")
      (node (ref "U$1") (pin "95") (pinfunction "PTB16_95") (pintype "bidirectional"))
    )
    (net (code "118") (name "unconnected-(U$1-PTB17-Pad96)") (class "Default")
      (node (ref "U$1") (pin "96") (pinfunction "PTB17_96") (pintype "bidirectional"))
    )
    (net (code "119") (name "unconnected-(U$1-PTB18-Pad97)") (class "Default")
      (node (ref "U$1") (pin "97") (pinfunction "PTB18_97") (pintype "bidirectional"))
    )
    (net (code "120") (name "unconnected-(U$1-PTB19-Pad98)") (class "Default")
      (node (ref "U$1") (pin "98") (pinfunction "PTB19_98") (pintype "bidirectional"))
    )
    (net (code "121") (name "unconnected-(U$1-PTB20-Pad99)") (class "Default")
      (node (ref "U$1") (pin "99") (pinfunction "PTB20_99") (pintype "bidirectional"))
    )
    (net (code "122") (name "unconnected-(U$1-PTB21-Pad100)") (class "Default")
      (node (ref "U$1") (pin "100") (pinfunction "PTB21_100") (pintype "bidirectional"))
    )
    (net (code "123") (name "unconnected-(U$1-PTB22-Pad101)") (class "Default")
      (node (ref "U$1") (pin "101") (pinfunction "PTB22_101") (pintype "bidirectional"))
    )
    (net (code "124") (name "unconnected-(U$1-PTC10-Pad115)") (class "Default")
      (node (ref "U$1") (pin "115") (pinfunction "PTC10_115") (pintype "bidirectional"))
    )
    (net (code "125") (name "unconnected-(U$1-PTC11-Pad116)") (class "Default")
      (node (ref "U$1") (pin "116") (pinfunction "PTC11_116") (pintype "bidirectional"))
    )
    (net (code "126") (name "unconnected-(U$1-PTC12-Pad117)") (class "Default")
      (node (ref "U$1") (pin "117") (pinfunction "PTC12_117") (pintype "bidirectional"))
    )
    (net (code "127") (name "unconnected-(U$1-PTC13-Pad118)") (class "Default")
      (node (ref "U$1") (pin "118") (pinfunction "PTC13_118") (pintype "bidirectional"))
    )
    (net (code "128") (name "unconnected-(U$1-PTC14-Pad119)") (class "Default")
      (node (ref "U$1") (pin "119") (pinfunction "PTC14_119") (pintype "bidirectional"))
    )
    (net (code "129") (name "unconnected-(U$1-PTC15-Pad120)") (class "Default")
      (node (ref "U$1") (pin "120") (pinfunction "PTC15_120") (pintype "bidirectional"))
    )
    (net (code "130") (name "unconnected-(U$1-PTC16-Pad123)") (class "Default")
      (node (ref "U$1") (pin "123") (pinfunction "PTC16_123") (pintype "bidirectional"))
    )
    (net (code "131") (name "unconnected-(U$1-PTC17-Pad124)") (class "Default")
      (node (ref "U$1") (pin "124") (pinfunction "PTC17_124") (pintype "bidirectional"))
    )
    (net (code "132") (name "unconnected-(U$1-PTC18-Pad125)") (class "Default")
      (node (ref "U$1") (pin "125") (pinfunction "PTC18_125") (pintype "bidirectional"))
    )
    (net (code "133") (name "unconnected-(U$1-PTC19-Pad126)") (class "Default")
      (node (ref "U$1") (pin "126") (pinfunction "PTC19_126") (pintype "bidirectional"))
    )
    (net (code "134") (name "unconnected-(U$1-PTD10-Pad139)") (class "Default")
      (node (ref "U$1") (pin "139") (pinfunction "PTD10_139") (pintype "bidirectional"))
    )
    (net (code "135") (name "unconnected-(U$1-PTD11-Pad140)") (class "Default")
      (node (ref "U$1") (pin "140") (pinfunction "PTD11_140") (pintype "bidirectional"))
    )
    (net (code "136") (name "unconnected-(U$1-PTD12-Pad141)") (class "Default")
      (node (ref "U$1") (pin "141") (pinfunction "PTD12_141") (pintype "bidirectional"))
    )
    (net (code "137") (name "unconnected-(U$1-PTD13-Pad142)") (class "Default")
      (node (ref "U$1") (pin "142") (pinfunction "PTD13_142") (pintype "bidirectional"))
    )
    (net (code "138") (name "unconnected-(U$1-PTD14-Pad143)") (class "Default")
      (node (ref "U$1") (pin "143") (pinfunction "PTD14_143") (pintype "bidirectional"))
    )
    (net (code "139") (name "unconnected-(U$1-PTD15-Pad144)") (class "Default")
      (node (ref "U$1") (pin "144") (pinfunction "PTD15_144") (pintype "bidirectional"))
    )
    (net (code "140") (name "unconnected-(U$1-PTE0-Pad1)") (class "Default")
      (node (ref "U$1") (pin "1") (pinfunction "PTE0_1") (pintype "bidirectional"))
    )
    (net (code "141") (name "unconnected-(U$1-PTE1-Pad2)") (class "Default")
      (node (ref "U$1") (pin "2") (pinfunction "PTE1_2") (pintype "bidirectional"))
    )
    (net (code "142") (name "unconnected-(U$1-PTE2-Pad3)") (class "Default")
      (node (ref "U$1") (pin "3") (pinfunction "PTE2_3") (pintype "bidirectional"))
    )
    (net (code "143") (name "unconnected-(U$1-PTE3-Pad4)") (class "Default")
      (node (ref "U$1") (pin "4") (pinfunction "PTE3_4") (pintype "bidirectional"))
    )
    (net (code "144") (name "unconnected-(U$1-PTE4-Pad7)") (class "Default")
      (node (ref "U$1") (pin "7") (pinfunction "PTE4_7") (pintype "bidirectional"))
    )
    (net (code "145") (name "unconnected-(U$1-PTE5-Pad8)") (class "Default")
      (node (ref "U$1") (pin "8") (pinfunction "PTE5_8") (pintype "bidirectional"))
    )
    (net (code "146") (name "unconnected-(U$1-PTE6-Pad9)") (class "Default")
      (node (ref "U$1") (pin "9") (pinfunction "PTE6_9") (pintype "bidirectional"))
    )
    (net (code "147") (name "unconnected-(U$1-PTE7-Pad10)") (class "Default")
      (node (ref "U$1") (pin "10") (pinfunction "PTE7_10") (pintype "bidirectional"))
    )
    (net (code "148") (name "unconnected-(U$1-PTE8-Pad11)") (class "Default")
      (node (ref "U$1") (pin "11") (pinfunction "PTE8_11") (pintype "bidirectional"))
    )
    (net (code "149") (name "unconnected-(U$1-PTE9-Pad12)") (class "Default")
      (node (ref "U$1") (pin "12") (pinfunction "PTE9_12") (pintype "bidirectional"))
    )
    (net (code "150") (name "unconnected-(U$1-PTE10-Pad13)") (class "Default")
      (node (ref "U$1") (pin "13") (pinfunction "PTE10_13") (pintype "bidirectional"))
    )
    (net (code "151") (name "unconnected-(U$1-PTE11-Pad14)") (class "Default")
      (node (ref "U$1") (pin "14") (pinfunction "PTE11_14") (pintype "bidirectional"))
    )
    (net (code "152") (name "unconnected-(U$1-PTE12-Pad15)") (class "Default")
      (node (ref "U$1") (pin "15") (pinfunction "PTE12_15") (pintype "bidirectional"))
    )
    (net (code "153") (name "unconnected-(U$1-PTE24-Pad45)") (class "Default")
      (node (ref "U$1") (pin "45") (pinfunction "PTE24_45") (pintype "output"))
    )
    (net (code "154") (name "unconnected-(U$1-PTE25-Pad46)") (class "Default")
      (node (ref "U$1") (pin "46") (pinfunction "PTE25_46") (pintype "input"))
    )
    (net (code "155") (name "unconnected-(U$1-PTE26-Pad47)") (class "Default")
      (node (ref "U$1") (pin "47") (pinfunction "PTE26_47") (pintype "bidirectional"))
    )
    (net (code "156") (name "unconnected-(U$1-PTE27-Pad48)") (class "Default")
      (node (ref "U$1") (pin "48") (pinfunction "PTE27_48") (pintype "bidirectional"))
    )
    (net (code "157") (name "unconnected-(U$1-PTE28-Pad49)") (class "Default")
      (node (ref "U$1") (pin "49") (pinfunction "PTE28_49") (pintype "bidirectional"))
    )
    (net (code "158") (name "unconnected-(USBFS-ID-Pad4)") (class "Default")
      (node (ref "USBFS") (pin "4") (pinfunction "ID_4") (pintype "input"))
    )
    (net (code "159") (name "unconnected-(USBHS-ID-Pad4)") (class "Default")
      (node (ref "USBHS") (pin "4") (pinfunction "ID_4") (pintype "input"))
    )
  )
)
